# DAPLink.net
KiCad netlist of a schematic drawn in Altium Designer
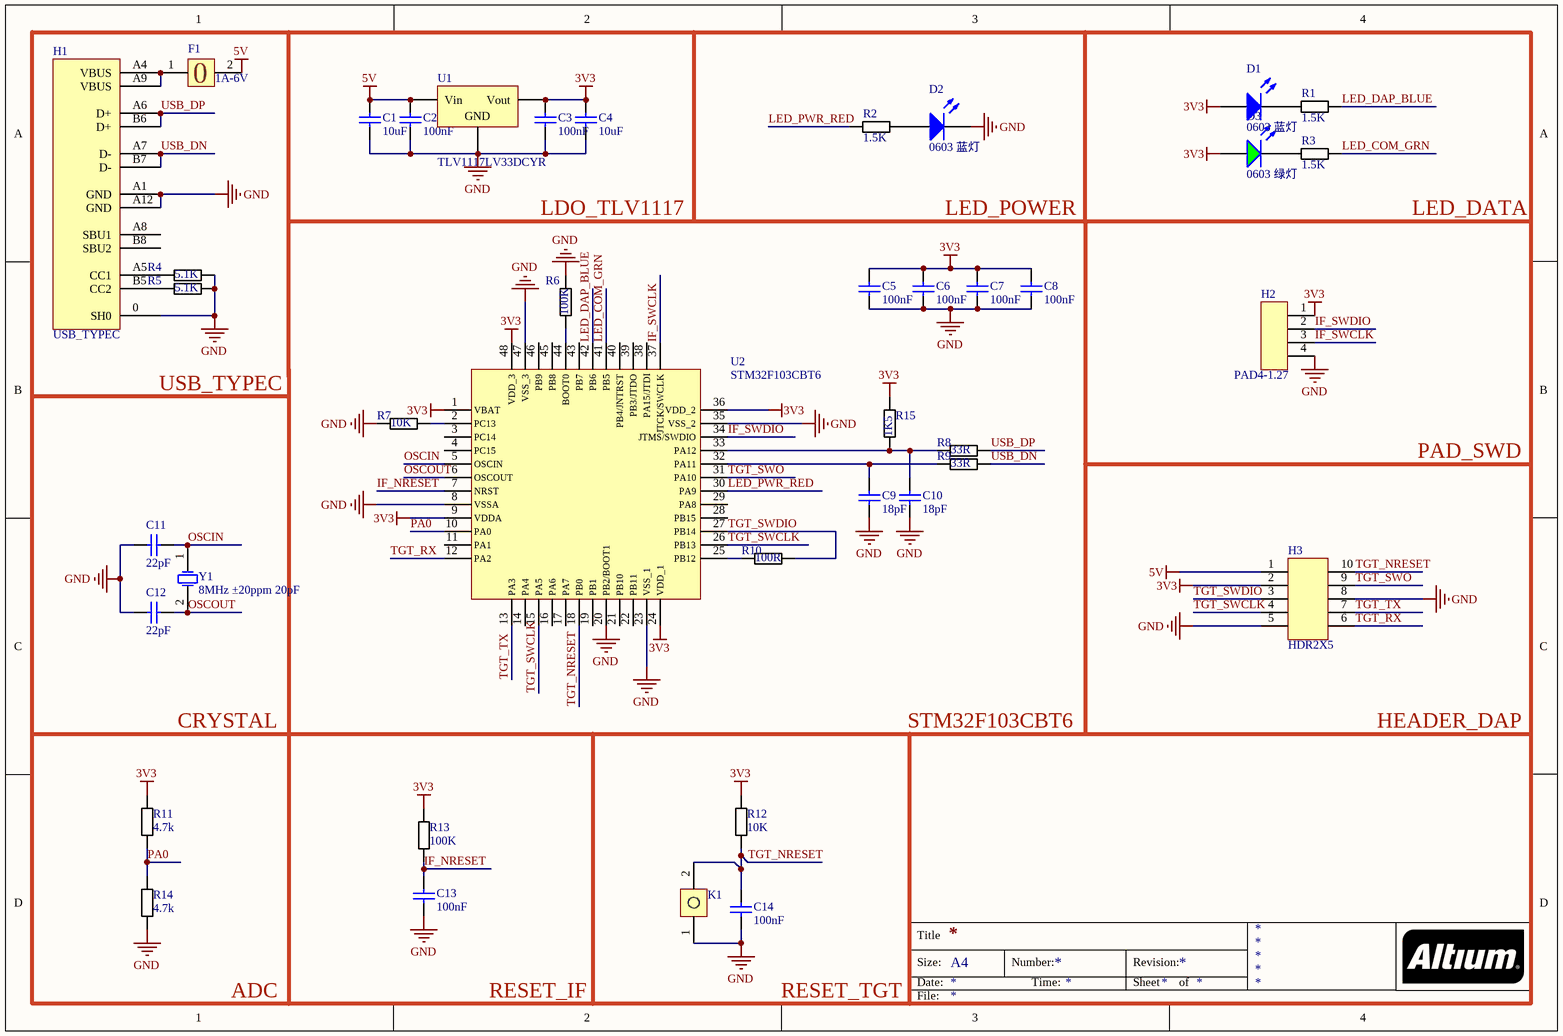
[diagram p0: DAPLink.SchDoc]

(export (version "E")
  (design (tool "Eeschema 10.0.6"))
  (components
    (comp (ref "C1")
      (value "10uF")
      (footprint "0603_C")
      (description "0603贴片电容 10UF(106) ±20% 25V")
      (libsource (lib "DAPLink") (part "CAP-0603"))
    )
    (comp (ref "C2")
      (value "100nF")
      (footprint "0603_C")
      (description "0603贴片电容 100NF (104) ±10% 50V X7R")
      (libsource (lib "DAPLink") (part "CAP-0603"))
    )
    (comp (ref "C3")
      (value "100nF")
      (footprint "0603_C")
      (description "0603贴片电容 100NF (104) ±10% 50V X7R")
      (libsource (lib "DAPLink") (part "CAP-0603"))
    )
    (comp (ref "C4")
      (value "10uF")
      (footprint "0603_C")
      (description "0603贴片电容 10UF(106) ±20% 25V")
      (libsource (lib "DAPLink") (part "CAP-0603"))
    )
    (comp (ref "C5")
      (value "100nF")
      (footprint "0603_C")
      (description "0603贴片电容 100NF (104) ±10% 50V X7R")
      (libsource (lib "DAPLink") (part "CAP-0603"))
    )
    (comp (ref "C6")
      (value "100nF")
      (footprint "0603_C")
      (description "0603贴片电容 100NF (104) ±10% 50V X7R")
      (libsource (lib "DAPLink") (part "CAP-0603"))
    )
    (comp (ref "C7")
      (value "100nF")
      (footprint "0603_C")
      (description "0603贴片电容 100NF (104) ±10% 50V X7R")
      (libsource (lib "DAPLink") (part "CAP-0603"))
    )
    (comp (ref "C8")
      (value "100nF")
      (footprint "0603_C")
      (description "0603贴片电容 100NF (104) ±10% 50V X7R")
      (libsource (lib "DAPLink") (part "CAP-0603"))
    )
    (comp (ref "C9")
      (value "18pF")
      (footprint "0603_C")
      (description "0603贴片电容 18PF (180) ±5% 50V C0G")
      (libsource (lib "DAPLink") (part "CAP-0603"))
    )
    (comp (ref "C10")
      (value "18pF")
      (footprint "0603_C")
      (description "0603贴片电容 18PF (180) ±5% 50V C0G")
      (libsource (lib "DAPLink") (part "CAP-0603"))
    )
    (comp (ref "C11")
      (value "22pF")
      (footprint "0603_C")
      (description "0603 贴片电容 22PF (220) ±5% 50V C0G")
      (libsource (lib "DAPLink") (part "CAP-0603"))
    )
    (comp (ref "C12")
      (value "22pF")
      (footprint "0603_C")
      (description "0603 贴片电容 22PF (220) ±5% 50V C0G")
      (libsource (lib "DAPLink") (part "CAP-0603"))
    )
    (comp (ref "C13")
      (value "100nF")
      (footprint "0603_C")
      (description "0603贴片电容 100NF (104) ±10% 50V X7R")
      (libsource (lib "DAPLink") (part "CAP-0603"))
    )
    (comp (ref "C14")
      (value "100nF")
      (footprint "0603_C")
      (description "0603贴片电容 100NF (104) ±10% 50V X7R")
      (libsource (lib "DAPLink") (part "CAP-0603"))
    )
    (comp (ref "D1")
      (value "0603 蓝灯")
      (footprint "0603_LED_BLUE")
      (description "发光二极管")
      (libsource (lib "DAPLink") (part "0603 蓝灯"))
    )
    (comp (ref "D2")
      (value "0603 蓝灯")
      (footprint "0603_LED_BLUE")
      (description "发光二极管")
      (libsource (lib "DAPLink") (part "0603 蓝灯"))
    )
    (comp (ref "D3")
      (value "0603 绿灯")
      (footprint "0603_LED_GREEN")
      (description "发光二极管")
      (libsource (lib "DAPLink") (part "0603 绿灯"))
    )
    (comp (ref "F1")
      (value "1A-6V")
      (footprint "0805_FUSE")
      (description "0805 1A 6V自恢复保险丝 SMD0805-100")
      (libsource (lib "DAPLink") (part "FUSE-0805"))
    )
    (comp (ref "H1")
      (value "USB_TYPEC")
      (footprint "USB_TYPEC")
      (libsource (lib "DAPLink") (part "USB_TYPEC"))
    )
    (comp (ref "H2")
      (value "PAD4-1.27")
      (footprint "HDR4-1.27")
      (libsource (lib "DAPLink") (part "PAD4-1.27"))
    )
    (comp (ref "H3")
      (value "HDR2X5")
      (footprint "HDR2X5_2.54_180H")
      (description "2.54双排排针")
      (libsource (lib "DAPLink") (part "HDR2X5_2.54_180H"))
    )
    (comp (ref "K1")
      (value "BUTTON_MINI")
      (footprint "BUTTON_MINI")
      (description "微动按键 龟仔")
      (libsource (lib "DAPLink") (part "BUTTON_MINI"))
    )
    (comp (ref "R1") (value "1.5K") (footprint "0603_R") (libsource (lib "") (part "RES-0603_1")))
    (comp (ref "R2") (value "1.5K") (footprint "0603_R") (libsource (lib "") (part "RES-0603_1")))
    (comp (ref "R3") (value "1.5K") (footprint "0603_R") (libsource (lib "") (part "RES-0603_1")))
    (comp (ref "R4") (value "5.1K") (footprint "0603_R") (libsource (lib "") (part "RES-0603_1")))
    (comp (ref "R5") (value "5.1K") (footprint "0603_R") (libsource (lib "") (part "RES-0603_1")))
    (comp (ref "R6") (value "100K") (footprint "0603_R") (libsource (lib "DAPLink") (part "RES-0603")))
    (comp (ref "R7") (value "10K") (footprint "0603_R") (libsource (lib "") (part "RES-0603_1")))
    (comp (ref "R8") (value "33R") (footprint "0603_R") (libsource (lib "") (part "RES-0603_1")))
    (comp (ref "R9") (value "33R") (footprint "0603_R") (libsource (lib "") (part "RES-0603_1")))
    (comp (ref "R10") (value "100R") (footprint "0603_R") (libsource (lib "") (part "RES-0603_1")))
    (comp (ref "R11") (value "4.7k") (footprint "0603_R") (libsource (lib "DAPLink") (part "RES-0603")))
    (comp (ref "R12") (value "10K") (footprint "0603_R") (libsource (lib "DAPLink") (part "RES-0603")))
    (comp (ref "R13") (value "100K") (footprint "0603_R") (libsource (lib "DAPLink") (part "RES-0603")))
    (comp (ref "R14") (value "4.7k") (footprint "0603_R") (libsource (lib "DAPLink") (part "RES-0603")))
    (comp (ref "R15") (value "1K5") (footprint "0603_R") (libsource (lib "DAPLink") (part "RES-0603")))
    (comp (ref "U1")
      (value "TLV1117LV33DCYR")
      (footprint "SOT-223")
      (description "低压差线性稳压(LDO)")
      (libsource (lib "DAPLink") (part "TLV1117LV33DCYR"))
    )
    (comp (ref "U2")
      (value "STM32F103CBT6")
      (footprint "LQFP-48_7x7x05P")
      (description "STM32F103CBT6   LQFP-48")
      (libsource (lib "DAPLink") (part "STM32F103CBT6"))
    )
    (comp (ref "Y1")
      (value "8MHz ±20ppm 20pF")
      (footprint "SMD-5032_2P")
      (description "5032贴片晶振，8MHz 20pF")
      (libsource (lib "DAPLink") (part "SMD-5032_2P 8MHz 20ppm 20pF"))
    )
  )
  (nets
    (net (code "1") (name "/IF_NRESET") (class "Default")
      (node (ref "C13") (pin "2") (pinfunction "2_2") (pintype "passive"))
      (node (ref "R13") (pin "1") (pinfunction "1_1") (pintype "passive"))
      (node (ref "U2") (pin "7") (pinfunction "NRST_7") (pintype "passive"))
    )
    (net (code "2") (name "/IF_SWCLK") (class "Default")
      (node (ref "H2") (pin "3") (pinfunction "3_3") (pintype "passive"))
      (node (ref "U2") (pin "37") (pinfunction "JTCK/SWCLK_37") (pintype "passive"))
    )
    (net (code "3") (name "/IF_SWDIO") (class "Default")
      (node (ref "H2") (pin "2") (pinfunction "2_2") (pintype "passive"))
      (node (ref "U2") (pin "34") (pinfunction "JTMS/SWDIO_34") (pintype "passive"))
    )
    (net (code "4") (name "/LED_COM_GRN") (class "Default")
      (node (ref "R3") (pin "2") (pinfunction "2_2") (pintype "passive"))
      (node (ref "U2") (pin "41") (pinfunction "PB5_41") (pintype "passive"))
    )
    (net (code "5") (name "/LED_DAP_BLUE") (class "Default")
      (node (ref "R1") (pin "2") (pinfunction "2_2") (pintype "passive"))
      (node (ref "U2") (pin "42") (pinfunction "PB6_42") (pintype "passive"))
    )
    (net (code "6") (name "/LED_PWR_RED") (class "Default")
      (node (ref "R2") (pin "1") (pinfunction "1_1") (pintype "passive"))
      (node (ref "U2") (pin "30") (pinfunction "PA9_30") (pintype "passive"))
    )
    (net (code "7") (name "/OSCIN") (class "Default")
      (node (ref "C11") (pin "2") (pinfunction "2_2") (pintype "passive"))
      (node (ref "U2") (pin "5") (pinfunction "OSCIN_5") (pintype "passive"))
      (node (ref "Y1") (pin "1") (pinfunction "OSC1_1") (pintype "passive"))
    )
    (net (code "8") (name "/OSCOUT") (class "Default")
      (node (ref "C12") (pin "2") (pinfunction "2_2") (pintype "passive"))
      (node (ref "U2") (pin "6") (pinfunction "OSCOUT_6") (pintype "passive"))
      (node (ref "Y1") (pin "2") (pinfunction "OSC2_2") (pintype "passive"))
    )
    (net (code "9") (name "/PA0") (class "Default")
      (node (ref "R11") (pin "1") (pinfunction "1_1") (pintype "passive"))
      (node (ref "R14") (pin "2") (pinfunction "2_2") (pintype "passive"))
      (node (ref "U2") (pin "10") (pinfunction "PA0_10") (pintype "passive"))
    )
    (net (code "10") (name "/TGT_NRESET") (class "Default")
      (node (ref "C14") (pin "2") (pinfunction "2_2") (pintype "passive"))
      (node (ref "H3") (pin "10") (pintype "passive"))
      (node (ref "K1") (pin "2") (pintype "passive"))
      (node (ref "R12") (pin "1") (pinfunction "1_1") (pintype "passive"))
      (node (ref "U2") (pin "18") (pinfunction "PB0_18") (pintype "passive"))
    )
    (net (code "11") (name "/TGT_RX") (class "Default")
      (node (ref "H3") (pin "6") (pintype "passive"))
      (node (ref "U2") (pin "12") (pinfunction "PA2_12") (pintype "passive"))
    )
    (net (code "12") (name "/TGT_SWCLK") (class "Default")
      (node (ref "H3") (pin "4") (pintype "passive"))
      (node (ref "U2") (pin "15") (pinfunction "PA5_15") (pintype "passive"))
      (node (ref "U2") (pin "26") (pinfunction "PB13_26") (pintype "passive"))
    )
    (net (code "13") (name "/TGT_SWDIO") (class "Default")
      (node (ref "H3") (pin "3") (pintype "passive"))
      (node (ref "R10") (pin "2") (pinfunction "2_2") (pintype "passive"))
      (node (ref "U2") (pin "27") (pinfunction "PB14_27") (pintype "passive"))
    )
    (net (code "14") (name "/TGT_SWO") (class "Default")
      (node (ref "H3") (pin "9") (pintype "passive"))
      (node (ref "U2") (pin "31") (pinfunction "PA10_31") (pintype "passive"))
    )
    (net (code "15") (name "/TGT_TX") (class "Default")
      (node (ref "H3") (pin "7") (pintype "passive"))
      (node (ref "U2") (pin "13") (pinfunction "PA3_13") (pintype "passive"))
    )
    (net (code "16") (name "/USB_DN") (class "Default")
      (node (ref "H1") (pin "A7") (pinfunction "D-_A7") (pintype "passive"))
      (node (ref "H1") (pin "B7") (pinfunction "D-_B7") (pintype "passive"))
      (node (ref "R9") (pin "2") (pinfunction "2_2") (pintype "passive"))
    )
    (net (code "17") (name "/USB_DP") (class "Default")
      (node (ref "H1") (pin "A6") (pinfunction "D+_A6") (pintype "passive"))
      (node (ref "H1") (pin "B6") (pinfunction "D+_B6") (pintype "passive"))
      (node (ref "R8") (pin "2") (pinfunction "2_2") (pintype "passive"))
    )
    (net (code "18") (name "3V3") (class "Default")
      (node (ref "C3") (pin "2") (pinfunction "2_2") (pintype "passive"))
      (node (ref "C4") (pin "2") (pinfunction "2_2") (pintype "passive"))
      (node (ref "C5") (pin "2") (pinfunction "2_2") (pintype "passive"))
      (node (ref "C6") (pin "2") (pinfunction "2_2") (pintype "passive"))
      (node (ref "C7") (pin "2") (pinfunction "2_2") (pintype "passive"))
      (node (ref "C8") (pin "2") (pinfunction "2_2") (pintype "passive"))
      (node (ref "D1") (pin "A") (pinfunction "A_A") (pintype "passive"))
      (node (ref "D3") (pin "A") (pinfunction "A_A") (pintype "passive"))
      (node (ref "H2") (pin "1") (pinfunction "1_1") (pintype "passive"))
      (node (ref "H3") (pin "2") (pintype "passive"))
      (node (ref "R11") (pin "2") (pinfunction "2_2") (pintype "passive"))
      (node (ref "R12") (pin "2") (pinfunction "2_2") (pintype "passive"))
      (node (ref "R13") (pin "2") (pinfunction "2_2") (pintype "passive"))
      (node (ref "R15") (pin "2") (pinfunction "2_2") (pintype "passive"))
      (node (ref "U1") (pin "2") (pinfunction "Vout_2") (pintype "passive"))
      (node (ref "U2") (pin "1") (pinfunction "VBAT_1") (pintype "passive"))
      (node (ref "U2") (pin "24") (pinfunction "VDD_1_24") (pintype "passive"))
      (node (ref "U2") (pin "36") (pinfunction "VDD_2_36") (pintype "passive"))
      (node (ref "U2") (pin "48") (pinfunction "VDD_3_48") (pintype "passive"))
      (node (ref "U2") (pin "9") (pinfunction "VDDA_9") (pintype "passive"))
    )
    (net (code "19") (name "5V") (class "Default")
      (node (ref "C1") (pin "2") (pinfunction "2_2") (pintype "passive"))
      (node (ref "C2") (pin "2") (pinfunction "2_2") (pintype "passive"))
      (node (ref "F1") (pin "2") (pintype "passive"))
      (node (ref "H3") (pin "1") (pintype "passive"))
      (node (ref "U1") (pin "3") (pinfunction "Vin_3") (pintype "passive"))
    )
    (net (code "20") (name "GND") (class "Default")
      (node (ref "C1") (pin "1") (pinfunction "1_1") (pintype "passive"))
      (node (ref "C10") (pin "1") (pinfunction "1_1") (pintype "passive"))
      (node (ref "C11") (pin "1") (pinfunction "1_1") (pintype "passive"))
      (node (ref "C12") (pin "1") (pinfunction "1_1") (pintype "passive"))
      (node (ref "C13") (pin "1") (pinfunction "1_1") (pintype "passive"))
      (node (ref "C14") (pin "1") (pinfunction "1_1") (pintype "passive"))
      (node (ref "C2") (pin "1") (pinfunction "1_1") (pintype "passive"))
      (node (ref "C3") (pin "1") (pinfunction "1_1") (pintype "passive"))
      (node (ref "C4") (pin "1") (pinfunction "1_1") (pintype "passive"))
      (node (ref "C5") (pin "1") (pinfunction "1_1") (pintype "passive"))
      (node (ref "C6") (pin "1") (pinfunction "1_1") (pintype "passive"))
      (node (ref "C7") (pin "1") (pinfunction "1_1") (pintype "passive"))
      (node (ref "C8") (pin "1") (pinfunction "1_1") (pintype "passive"))
      (node (ref "C9") (pin "1") (pinfunction "1_1") (pintype "passive"))
      (node (ref "D2") (pin "K") (pinfunction "K_K") (pintype "passive"))
      (node (ref "H1") (pin "0") (pinfunction "SH0_0") (pintype "passive"))
      (node (ref "H1") (pin "A1") (pinfunction "GND_A1") (pintype "passive"))
      (node (ref "H1") (pin "A12") (pinfunction "GND_A12") (pintype "passive"))
      (node (ref "H2") (pin "4") (pinfunction "4_4") (pintype "passive"))
      (node (ref "H3") (pin "5") (pintype "passive"))
      (node (ref "H3") (pin "8") (pintype "passive"))
      (node (ref "K1") (pin "1") (pintype "passive"))
      (node (ref "R14") (pin "1") (pinfunction "1_1") (pintype "passive"))
      (node (ref "R4") (pin "2") (pinfunction "2_2") (pintype "passive"))
      (node (ref "R5") (pin "2") (pinfunction "2_2") (pintype "passive"))
      (node (ref "R6") (pin "2") (pinfunction "2_2") (pintype "passive"))
      (node (ref "R7") (pin "1") (pinfunction "1_1") (pintype "passive"))
      (node (ref "U1") (pin "1") (pinfunction "GND_1") (pintype "passive"))
      (node (ref "U2") (pin "20") (pinfunction "PB2/BOOT1_20") (pintype "passive"))
      (node (ref "U2") (pin "23") (pinfunction "VSS_1_23") (pintype "passive"))
      (node (ref "U2") (pin "35") (pinfunction "VSS_2_35") (pintype "passive"))
      (node (ref "U2") (pin "47") (pinfunction "VSS_3_47") (pintype "passive"))
      (node (ref "U2") (pin "8") (pinfunction "VSSA_8") (pintype "passive"))
    )
    (net (code "21") (name "Net-(D1-PadK)") (class "Default")
      (node (ref "D1") (pin "K") (pinfunction "K_K") (pintype "passive"))
      (node (ref "R1") (pin "1") (pinfunction "1_1") (pintype "passive"))
    )
    (net (code "22") (name "Net-(D2-PadA)") (class "Default")
      (node (ref "D2") (pin "A") (pinfunction "A_A") (pintype "passive"))
      (node (ref "R2") (pin "2") (pinfunction "2_2") (pintype "passive"))
    )
    (net (code "23") (name "Net-(D3-PadK)") (class "Default")
      (node (ref "D3") (pin "K") (pinfunction "K_K") (pintype "passive"))
      (node (ref "R3") (pin "1") (pinfunction "1_1") (pintype "passive"))
    )
    (net (code "24") (name "Net-(F1-Pad1)") (class "Default")
      (node (ref "F1") (pin "1") (pintype "passive"))
      (node (ref "H1") (pin "A4") (pinfunction "VBUS_A4") (pintype "passive"))
      (node (ref "H1") (pin "A9") (pinfunction "VBUS_A9") (pintype "passive"))
    )
    (net (code "25") (name "Net-(H1-CC1)") (class "Default")
      (node (ref "H1") (pin "A5") (pinfunction "CC1_A5") (pintype "passive"))
      (node (ref "R4") (pin "1") (pinfunction "1_1") (pintype "passive"))
    )
    (net (code "26") (name "Net-(H1-CC2)") (class "Default")
      (node (ref "H1") (pin "B5") (pinfunction "CC2_B5") (pintype "passive"))
      (node (ref "R5") (pin "1") (pinfunction "1_1") (pintype "passive"))
    )
    (net (code "27") (name "Net-(U2-BOOT0)") (class "Default")
      (node (ref "R6") (pin "1") (pinfunction "1_1") (pintype "passive"))
      (node (ref "U2") (pin "44") (pinfunction "BOOT0_44") (pintype "passive"))
    )
    (net (code "28") (name "Net-(U2-PA11)") (class "Default")
      (node (ref "C9") (pin "2") (pinfunction "2_2") (pintype "passive"))
      (node (ref "R9") (pin "1") (pinfunction "1_1") (pintype "passive"))
      (node (ref "U2") (pin "32") (pinfunction "PA11_32") (pintype "passive"))
    )
    (net (code "29") (name "Net-(U2-PA12)") (class "Default")
      (node (ref "C10") (pin "2") (pinfunction "2_2") (pintype "passive"))
      (node (ref "R15") (pin "1") (pinfunction "1_1") (pintype "passive"))
      (node (ref "R8") (pin "1") (pinfunction "1_1") (pintype "passive"))
      (node (ref "U2") (pin "33") (pinfunction "PA12_33") (pintype "passive"))
    )
    (net (code "30") (name "Net-(U2-PB12)") (class "Default")
      (node (ref "R10") (pin "1") (pinfunction "1_1") (pintype "passive"))
      (node (ref "U2") (pin "25") (pinfunction "PB12_25") (pintype "passive"))
    )
    (net (code "31") (name "Net-(U2-PC13)") (class "Default")
      (node (ref "R7") (pin "2") (pinfunction "2_2") (pintype "passive"))
      (node (ref "U2") (pin "2") (pinfunction "PC13_2") (pintype "passive"))
    )
    (net (code "32") (name "unconnected-(H1-SBU1-PadA8)") (class "Default")
      (node (ref "H1") (pin "A8") (pinfunction "SBU1_A8") (pintype "passive"))
    )
    (net (code "33") (name "unconnected-(H1-SBU2-PadB8)") (class "Default")
      (node (ref "H1") (pin "B8") (pinfunction "SBU2_B8") (pintype "passive"))
    )
    (net (code "34") (name "unconnected-(U2-PA1-Pad11)") (class "Default")
      (node (ref "U2") (pin "11") (pinfunction "PA1_11") (pintype "passive"))
    )
    (net (code "35") (name "unconnected-(U2-PA4-Pad14)") (class "Default")
      (node (ref "U2") (pin "14") (pinfunction "PA4_14") (pintype "passive"))
    )
    (net (code "36") (name "unconnected-(U2-PA6-Pad16)") (class "Default")
      (node (ref "U2") (pin "16") (pinfunction "PA6_16") (pintype "passive"))
    )
    (net (code "37") (name "unconnected-(U2-PA7-Pad17)") (class "Default")
      (node (ref "U2") (pin "17") (pinfunction "PA7_17") (pintype "passive"))
    )
    (net (code "38") (name "unconnected-(U2-PA8-Pad29)") (class "Default")
      (node (ref "U2") (pin "29") (pinfunction "PA8_29") (pintype "passive"))
    )
    (net (code "39") (name "unconnected-(U2-PA15{slash}JTDI-Pad38)") (class "Default")
      (node (ref "U2") (pin "38") (pinfunction "PA15/JTDI_38") (pintype "passive"))
    )
    (net (code "40") (name "unconnected-(U2-PB1-Pad19)") (class "Default")
      (node (ref "U2") (pin "19") (pinfunction "PB1_19") (pintype "passive"))
    )
    (net (code "41") (name "unconnected-(U2-PB3{slash}JTDO-Pad39)") (class "Default")
      (node (ref "U2") (pin "39") (pinfunction "PB3/JTDO_39") (pintype "passive"))
    )
    (net (code "42") (name "unconnected-(U2-PB4{slash}JNTRST-Pad40)") (class "Default")
      (node (ref "U2") (pin "40") (pinfunction "PB4/JNTRST_40") (pintype "passive"))
    )
    (net (code "43") (name "unconnected-(U2-PB7-Pad43)") (class "Default")
      (node (ref "U2") (pin "43") (pinfunction "PB7_43") (pintype "passive"))
    )
    (net (code "44") (name "unconnected-(U2-PB8-Pad45)") (class "Default")
      (node (ref "U2") (pin "45") (pinfunction "PB8_45") (pintype "passive"))
    )
    (net (code "45") (name "unconnected-(U2-PB9-Pad46)") (class "Default")
      (node (ref "U2") (pin "46") (pinfunction "PB9_46") (pintype "passive"))
    )
    (net (code "46") (name "unconnected-(U2-PB10-Pad21)") (class "Default")
      (node (ref "U2") (pin "21") (pinfunction "PB10_21") (pintype "passive"))
    )
    (net (code "47") (name "unconnected-(U2-PB11-Pad22)") (class "Default")
      (node (ref "U2") (pin "22") (pinfunction "PB11_22") (pintype "passive"))
    )
    (net (code "48") (name "unconnected-(U2-PB15-Pad28)") (class "Default")
      (node (ref "U2") (pin "28") (pinfunction "PB15_28") (pintype "passive"))
    )
    (net (code "49") (name "unconnected-(U2-PC14-Pad3)") (class "Default")
      (node (ref "U2") (pin "3") (pinfunction "PC14_3") (pintype "passive"))
    )
    (net (code "50") (name "unconnected-(U2-PC15-Pad4)") (class "Default")
      (node (ref "U2") (pin "4") (pinfunction "PC15_4") (pintype "passive"))
    )
  )
)
